# RGB-driver-v1.net
KiCad netlist of a schematic drawn in EAGLE
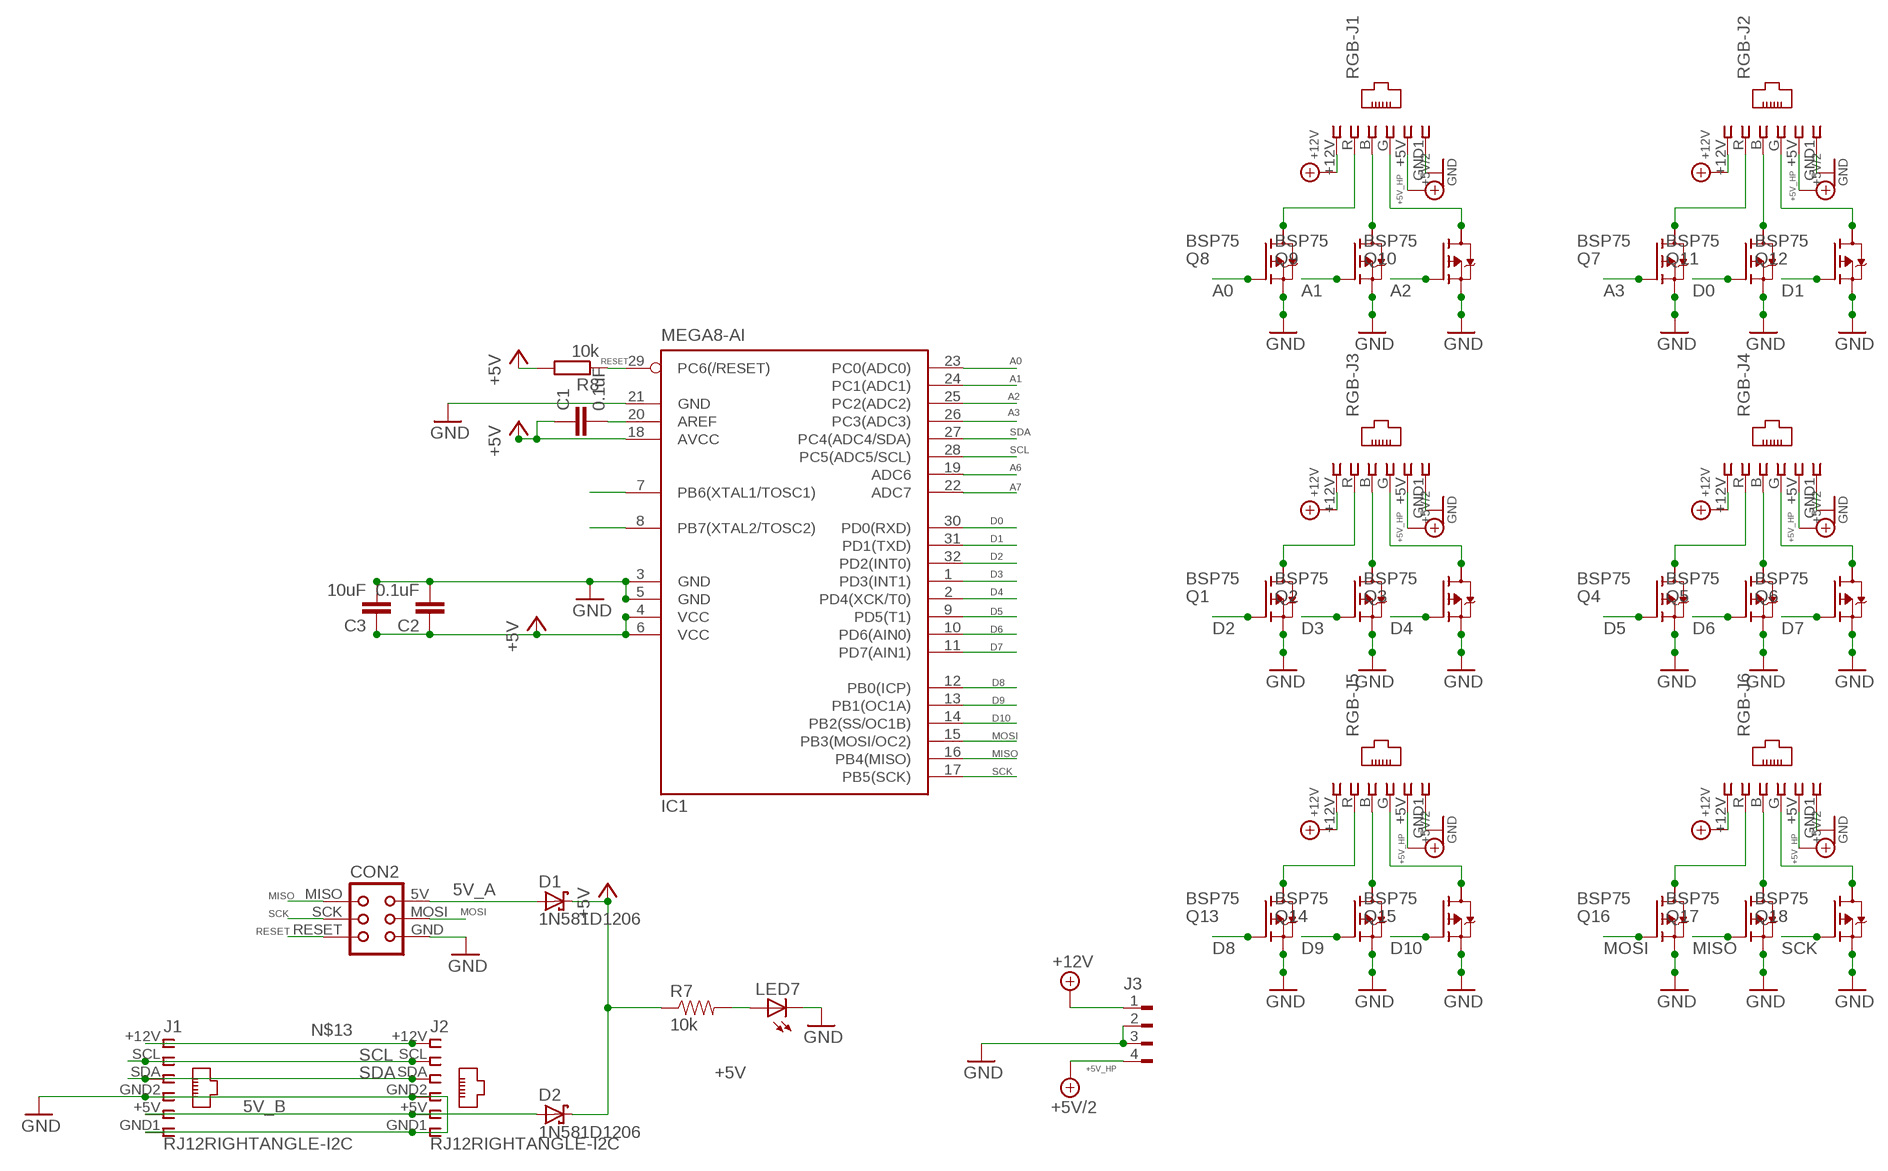
[diagram p0: schematic, sheet 1]

(export (version "E")
  (design (tool "Eeschema 10.0.6"))
  (components
    (comp (ref "C1")
      (value "0.1uF")
      (footprint "eagle-import:C1206")
      (libsource (lib "eagle-import") (part "C-EUC1206"))
    )
    (comp (ref "C2")
      (value "0.1uF")
      (footprint "eagle-import:C1206")
      (libsource (lib "eagle-import") (part "C-EUC1206"))
    )
    (comp (ref "C3")
      (value "10uF")
      (footprint "eagle-import:C1206")
      (libsource (lib "eagle-import") (part "C-EUC1206"))
    )
    (comp (ref "CON2")
      (value "TINYISPTAG")
      (footprint "eagle-import:TC2030-MCP")
      (libsource (lib "eagle-import") (part "TINYISPTAG"))
    )
    (comp (ref "D1")
      (value "1N581D1206")
      (footprint "eagle-import:LED-1206")
      (libsource (lib "eagle-import") (part "1N581D1206"))
    )
    (comp (ref "D2")
      (value "1N581D1206")
      (footprint "eagle-import:LED-1206")
      (libsource (lib "eagle-import") (part "1N581D1206"))
    )
    (comp (ref "IC1")
      (value "MEGA8-AI")
      (footprint "eagle-import:TQFP32-08")
      (fields (field (name "MPN") "ATMEGA8-16AU"))
      (libsource (lib "eagle-import") (part "MEGA8-AI"))
    )
    (comp (ref "J1")
      (value "RJ12RIGHTANGLE-I2C")
      (footprint "eagle-import:RJ12-RIGHTANGLE-I2C")
      (libsource (lib "eagle-import") (part "RJ12RIGHTANGLE-I2C"))
    )
    (comp (ref "J2")
      (value "RJ12RIGHTANGLE-I2C")
      (footprint "eagle-import:RJ12-RIGHTANGLE-I2C")
      (libsource (lib "eagle-import") (part "RJ12RIGHTANGLE-I2C"))
    )
    (comp (ref "J3")
      (value "FLOP-4W827001")
      (footprint "eagle-import:827001")
      (libsource (lib "eagle-import") (part "FLOP-4W827001"))
    )
    (comp (ref "LED7")
      (value "LEDCHIP-LED0603")
      (footprint "eagle-import:CHIP-LED0603")
      (libsource (lib "eagle-import") (part "LEDCHIP-LED0603"))
    )
    (comp (ref "Q1")
      (value "BSP75")
      (footprint "eagle-import:PG-SOT-223")
      (libsource (lib "eagle-import") (part "BSP613P"))
    )
    (comp (ref "Q2")
      (value "BSP75")
      (footprint "eagle-import:PG-SOT-223")
      (libsource (lib "eagle-import") (part "BSP613P"))
    )
    (comp (ref "Q3")
      (value "BSP75")
      (footprint "eagle-import:PG-SOT-223")
      (libsource (lib "eagle-import") (part "BSP613P"))
    )
    (comp (ref "Q4")
      (value "BSP75")
      (footprint "eagle-import:PG-SOT-223")
      (libsource (lib "eagle-import") (part "BSP613P"))
    )
    (comp (ref "Q5")
      (value "BSP75")
      (footprint "eagle-import:PG-SOT-223")
      (libsource (lib "eagle-import") (part "BSP613P"))
    )
    (comp (ref "Q6")
      (value "BSP75")
      (footprint "eagle-import:PG-SOT-223")
      (libsource (lib "eagle-import") (part "BSP613P"))
    )
    (comp (ref "Q7")
      (value "BSP75")
      (footprint "eagle-import:PG-SOT-223")
      (libsource (lib "eagle-import") (part "BSP613P"))
    )
    (comp (ref "Q8")
      (value "BSP75")
      (footprint "eagle-import:PG-SOT-223")
      (libsource (lib "eagle-import") (part "BSP613P"))
    )
    (comp (ref "Q9")
      (value "BSP75")
      (footprint "eagle-import:PG-SOT-223")
      (libsource (lib "eagle-import") (part "BSP613P"))
    )
    (comp (ref "Q10")
      (value "BSP75")
      (footprint "eagle-import:PG-SOT-223")
      (libsource (lib "eagle-import") (part "BSP613P"))
    )
    (comp (ref "Q11")
      (value "BSP75")
      (footprint "eagle-import:PG-SOT-223")
      (libsource (lib "eagle-import") (part "BSP613P"))
    )
    (comp (ref "Q12")
      (value "BSP75")
      (footprint "eagle-import:PG-SOT-223")
      (libsource (lib "eagle-import") (part "BSP613P"))
    )
    (comp (ref "Q13")
      (value "BSP75")
      (footprint "eagle-import:PG-SOT-223")
      (libsource (lib "eagle-import") (part "BSP613P"))
    )
    (comp (ref "Q14")
      (value "BSP75")
      (footprint "eagle-import:PG-SOT-223")
      (libsource (lib "eagle-import") (part "BSP613P"))
    )
    (comp (ref "Q15")
      (value "BSP75")
      (footprint "eagle-import:PG-SOT-223")
      (libsource (lib "eagle-import") (part "BSP613P"))
    )
    (comp (ref "Q16")
      (value "BSP75")
      (footprint "eagle-import:PG-SOT-223")
      (libsource (lib "eagle-import") (part "BSP613P"))
    )
    (comp (ref "Q17")
      (value "BSP75")
      (footprint "eagle-import:PG-SOT-223")
      (libsource (lib "eagle-import") (part "BSP613P"))
    )
    (comp (ref "Q18")
      (value "BSP75")
      (footprint "eagle-import:PG-SOT-223")
      (libsource (lib "eagle-import") (part "BSP613P"))
    )
    (comp (ref "R7")
      (value "10k")
      (footprint "eagle-import:0603-RES")
      (libsource (lib "eagle-import") (part "RESISTOR0603-RES"))
    )
    (comp (ref "R8")
      (value "10k")
      (footprint "eagle-import:M1206")
      (libsource (lib "eagle-import") (part "R-EU_M1206"))
    )
    (comp (ref "RGB-J1")
      (value "RJ12")
      (footprint "eagle-import:RJ12-STRAIGHT-RGB")
      (libsource (lib "eagle-import") (part "RJ12STRAIGHT-RGB"))
    )
    (comp (ref "RGB-J2")
      (value "RJ12")
      (footprint "eagle-import:RJ12-STRAIGHT-RGB")
      (libsource (lib "eagle-import") (part "RJ12STRAIGHT-RGB"))
    )
    (comp (ref "RGB-J3")
      (value "RJ12")
      (footprint "eagle-import:RJ12-STRAIGHT-RGB")
      (libsource (lib "eagle-import") (part "RJ12STRAIGHT-RGB"))
    )
    (comp (ref "RGB-J4")
      (value "RJ12")
      (footprint "eagle-import:RJ12-STRAIGHT-RGB")
      (libsource (lib "eagle-import") (part "RJ12STRAIGHT-RGB"))
    )
    (comp (ref "RGB-J5")
      (value "RJ12")
      (footprint "eagle-import:RJ12-STRAIGHT-RGB")
      (libsource (lib "eagle-import") (part "RJ12STRAIGHT-RGB"))
    )
    (comp (ref "RGB-J6")
      (value "RJ12")
      (footprint "eagle-import:RJ12-STRAIGHT-RGB")
      (libsource (lib "eagle-import") (part "RJ12STRAIGHT-RGB"))
    )
  )
  (nets
    (net (code "1") (name "+5V") (class "Default")
      (node (ref "C1") (pin "1") (pinfunction "1_1") (pintype "passive"))
      (node (ref "C2") (pin "1") (pinfunction "1_1") (pintype "passive"))
      (node (ref "C3") (pin "1") (pinfunction "1_1") (pintype "passive"))
      (node (ref "D1") (pin "C") (pinfunction "C_C") (pintype "passive"))
      (node (ref "D2") (pin "C") (pinfunction "C_C") (pintype "passive"))
      (node (ref "IC1") (pin "18") (pinfunction "AVCC_18") (pintype "power_in"))
      (node (ref "IC1") (pin "4") (pinfunction "VCC_4") (pintype "power_in"))
      (node (ref "IC1") (pin "6") (pinfunction "VCC_6") (pintype "power_in"))
      (node (ref "R7") (pin "1") (pinfunction "1_1") (pintype "passive"))
      (node (ref "R8") (pin "2") (pinfunction "2_2") (pintype "passive"))
    )
    (net (code "2") (name "+5V{slash}2") (class "Default")
      (node (ref "J3") (pin "4") (pinfunction "4_4") (pintype "passive"))
      (node (ref "RGB-J1") (pin "+5V") (pinfunction "5_+5V") (pintype "bidirectional"))
      (node (ref "RGB-J2") (pin "+5V") (pinfunction "5_+5V") (pintype "bidirectional"))
      (node (ref "RGB-J3") (pin "+5V") (pinfunction "5_+5V") (pintype "bidirectional"))
      (node (ref "RGB-J4") (pin "+5V") (pinfunction "5_+5V") (pintype "bidirectional"))
      (node (ref "RGB-J5") (pin "+5V") (pinfunction "5_+5V") (pintype "bidirectional"))
      (node (ref "RGB-J6") (pin "+5V") (pinfunction "5_+5V") (pintype "bidirectional"))
    )
    (net (code "3") (name "+12V") (class "Default")
      (node (ref "J3") (pin "1") (pinfunction "1_1") (pintype "passive"))
      (node (ref "RGB-J1") (pin "+12V") (pinfunction "1_+12V") (pintype "bidirectional"))
      (node (ref "RGB-J2") (pin "+12V") (pinfunction "1_+12V") (pintype "bidirectional"))
      (node (ref "RGB-J3") (pin "+12V") (pinfunction "1_+12V") (pintype "bidirectional"))
      (node (ref "RGB-J4") (pin "+12V") (pinfunction "1_+12V") (pintype "bidirectional"))
      (node (ref "RGB-J5") (pin "+12V") (pinfunction "1_+12V") (pintype "bidirectional"))
      (node (ref "RGB-J6") (pin "+12V") (pinfunction "1_+12V") (pintype "bidirectional"))
    )
    (net (code "4") (name "/5V_A") (class "Default")
      (node (ref "CON2") (pin "5V") (pinfunction "VCC_5V") (pintype "passive"))
      (node (ref "D1") (pin "A") (pinfunction "A_A") (pintype "passive"))
    )
    (net (code "5") (name "/5V_B") (class "Default")
      (node (ref "D2") (pin "A") (pinfunction "A_A") (pintype "passive"))
      (node (ref "J1") (pin "+5V") (pinfunction "5_+5V") (pintype "bidirectional"))
      (node (ref "J2") (pin "+5V") (pinfunction "5_+5V") (pintype "bidirectional"))
    )
    (net (code "6") (name "/A0") (class "Default")
      (node (ref "IC1") (pin "23") (pinfunction "PC0(ADC0)_23") (pintype "bidirectional"))
      (node (ref "Q8") (pin "1") (pinfunction "G_1") (pintype "passive"))
    )
    (net (code "7") (name "/A1") (class "Default")
      (node (ref "IC1") (pin "24") (pinfunction "PC1(ADC1)_24") (pintype "bidirectional"))
      (node (ref "Q9") (pin "1") (pinfunction "G_1") (pintype "passive"))
    )
    (net (code "8") (name "/A2") (class "Default")
      (node (ref "IC1") (pin "25") (pinfunction "PC2(ADC2)_25") (pintype "bidirectional"))
      (node (ref "Q10") (pin "1") (pinfunction "G_1") (pintype "passive"))
    )
    (net (code "9") (name "/A3") (class "Default")
      (node (ref "IC1") (pin "26") (pinfunction "PC3(ADC3)_26") (pintype "bidirectional"))
      (node (ref "Q7") (pin "1") (pinfunction "G_1") (pintype "passive"))
    )
    (net (code "10") (name "/A6") (class "Default")
      (node (ref "IC1") (pin "19") (pinfunction "ADC6_19") (pintype "bidirectional"))
    )
    (net (code "11") (name "/A7") (class "Default")
      (node (ref "IC1") (pin "22") (pinfunction "ADC7_22") (pintype "bidirectional"))
    )
    (net (code "12") (name "/D0") (class "Default")
      (node (ref "IC1") (pin "30") (pinfunction "PD0(RXD)_30") (pintype "bidirectional"))
      (node (ref "Q11") (pin "1") (pinfunction "G_1") (pintype "passive"))
    )
    (net (code "13") (name "/D1") (class "Default")
      (node (ref "IC1") (pin "31") (pinfunction "PD1(TXD)_31") (pintype "bidirectional"))
      (node (ref "Q12") (pin "1") (pinfunction "G_1") (pintype "passive"))
    )
    (net (code "14") (name "/D2") (class "Default")
      (node (ref "IC1") (pin "32") (pinfunction "PD2(INT0)_32") (pintype "bidirectional"))
      (node (ref "Q1") (pin "1") (pinfunction "G_1") (pintype "passive"))
    )
    (net (code "15") (name "/D3") (class "Default")
      (node (ref "IC1") (pin "1") (pinfunction "PD3(INT1)_1") (pintype "bidirectional"))
      (node (ref "Q2") (pin "1") (pinfunction "G_1") (pintype "passive"))
    )
    (net (code "16") (name "/D4") (class "Default")
      (node (ref "IC1") (pin "2") (pinfunction "PD4(XCK/T0)_2") (pintype "bidirectional"))
      (node (ref "Q3") (pin "1") (pinfunction "G_1") (pintype "passive"))
    )
    (net (code "17") (name "/D5") (class "Default")
      (node (ref "IC1") (pin "9") (pinfunction "PD5(T1)_9") (pintype "bidirectional"))
      (node (ref "Q4") (pin "1") (pinfunction "G_1") (pintype "passive"))
    )
    (net (code "18") (name "/D6") (class "Default")
      (node (ref "IC1") (pin "10") (pinfunction "PD6(AIN0)_10") (pintype "bidirectional"))
      (node (ref "Q5") (pin "1") (pinfunction "G_1") (pintype "passive"))
    )
    (net (code "19") (name "/D7") (class "Default")
      (node (ref "IC1") (pin "11") (pinfunction "PD7(AIN1)_11") (pintype "bidirectional"))
      (node (ref "Q6") (pin "1") (pinfunction "G_1") (pintype "passive"))
    )
    (net (code "20") (name "/D8") (class "Default")
      (node (ref "IC1") (pin "12") (pinfunction "PB0(ICP)_12") (pintype "bidirectional"))
      (node (ref "Q13") (pin "1") (pinfunction "G_1") (pintype "passive"))
    )
    (net (code "21") (name "/D9") (class "Default")
      (node (ref "IC1") (pin "13") (pinfunction "PB1(OC1A)_13") (pintype "bidirectional"))
      (node (ref "Q14") (pin "1") (pinfunction "G_1") (pintype "passive"))
    )
    (net (code "22") (name "/D10") (class "Default")
      (node (ref "IC1") (pin "14") (pinfunction "PB2(SS/OC1B)_14") (pintype "bidirectional"))
      (node (ref "Q15") (pin "1") (pinfunction "G_1") (pintype "passive"))
    )
    (net (code "23") (name "/MISO") (class "Default")
      (node (ref "CON2") (pin "MISO") (pinfunction "MISO_MISO") (pintype "passive"))
      (node (ref "IC1") (pin "16") (pinfunction "PB4(MISO)_16") (pintype "bidirectional"))
      (node (ref "Q17") (pin "1") (pinfunction "G_1") (pintype "passive"))
    )
    (net (code "24") (name "/MOSI") (class "Default")
      (node (ref "CON2") (pin "MOSI") (pinfunction "MOSI_MOSI") (pintype "passive"))
      (node (ref "IC1") (pin "15") (pinfunction "PB3(MOSI/OC2)_15") (pintype "bidirectional"))
      (node (ref "Q16") (pin "1") (pinfunction "G_1") (pintype "passive"))
    )
    (net (code "25") (name "/N$13") (class "Default")
      (node (ref "J1") (pin "+12V") (pinfunction "1_+12V") (pintype "bidirectional"))
      (node (ref "J2") (pin "+12V") (pinfunction "1_+12V") (pintype "bidirectional"))
    )
    (net (code "26") (name "/RESET") (class "Default")
      (node (ref "CON2") (pin "RESET") (pinfunction "RESET_RESET") (pintype "passive"))
      (node (ref "IC1") (pin "29") (pinfunction "PC6(/RESET)_29") (pintype "bidirectional"))
      (node (ref "R8") (pin "1") (pinfunction "1_1") (pintype "passive"))
    )
    (net (code "27") (name "/SCK") (class "Default")
      (node (ref "CON2") (pin "SCK") (pinfunction "SCK_SCK") (pintype "passive"))
      (node (ref "IC1") (pin "17") (pinfunction "PB5(SCK)_17") (pintype "bidirectional"))
      (node (ref "Q18") (pin "1") (pinfunction "G_1") (pintype "passive"))
    )
    (net (code "28") (name "/SCL") (class "Default")
      (node (ref "IC1") (pin "28") (pinfunction "PC5(ADC5/SCL)_28") (pintype "bidirectional"))
      (node (ref "J1") (pin "SCL") (pinfunction "2_SCL") (pintype "bidirectional"))
      (node (ref "J2") (pin "SCL") (pinfunction "2_SCL") (pintype "bidirectional"))
    )
    (net (code "29") (name "/SDA") (class "Default")
      (node (ref "IC1") (pin "27") (pinfunction "PC4(ADC4/SDA)_27") (pintype "bidirectional"))
      (node (ref "J1") (pin "SDA") (pinfunction "3_SDA") (pintype "bidirectional"))
      (node (ref "J2") (pin "SDA") (pinfunction "3_SDA") (pintype "bidirectional"))
    )
    (net (code "30") (name "GND") (class "Default")
      (node (ref "C2") (pin "2") (pinfunction "2_2") (pintype "passive"))
      (node (ref "C3") (pin "2") (pinfunction "2_2") (pintype "passive"))
      (node (ref "CON2") (pin "GND") (pinfunction "GND_GND") (pintype "passive"))
      (node (ref "IC1") (pin "21") (pinfunction "GND_21") (pintype "power_in"))
      (node (ref "IC1") (pin "3") (pinfunction "GND_3") (pintype "power_in"))
      (node (ref "IC1") (pin "5") (pinfunction "GND_5") (pintype "power_in"))
      (node (ref "J1") (pin "GND1") (pinfunction "6_GND1") (pintype "bidirectional"))
      (node (ref "J1") (pin "GND2") (pinfunction "4_GND2") (pintype "bidirectional"))
      (node (ref "J2") (pin "GND1") (pinfunction "6_GND1") (pintype "bidirectional"))
      (node (ref "J2") (pin "GND2") (pinfunction "4_GND2") (pintype "bidirectional"))
      (node (ref "J3") (pin "2") (pinfunction "2_2") (pintype "passive"))
      (node (ref "J3") (pin "3") (pinfunction "3_3") (pintype "passive"))
      (node (ref "LED7") (pin "C") (pinfunction "C_C") (pintype "passive"))
      (node (ref "Q1") (pin "3") (pinfunction "S_3") (pintype "passive"))
      (node (ref "Q10") (pin "3") (pinfunction "S_3") (pintype "passive"))
      (node (ref "Q11") (pin "3") (pinfunction "S_3") (pintype "passive"))
      (node (ref "Q12") (pin "3") (pinfunction "S_3") (pintype "passive"))
      (node (ref "Q13") (pin "3") (pinfunction "S_3") (pintype "passive"))
      (node (ref "Q14") (pin "3") (pinfunction "S_3") (pintype "passive"))
      (node (ref "Q15") (pin "3") (pinfunction "S_3") (pintype "passive"))
      (node (ref "Q16") (pin "3") (pinfunction "S_3") (pintype "passive"))
      (node (ref "Q17") (pin "3") (pinfunction "S_3") (pintype "passive"))
      (node (ref "Q18") (pin "3") (pinfunction "S_3") (pintype "passive"))
      (node (ref "Q2") (pin "3") (pinfunction "S_3") (pintype "passive"))
      (node (ref "Q3") (pin "3") (pinfunction "S_3") (pintype "passive"))
      (node (ref "Q4") (pin "3") (pinfunction "S_3") (pintype "passive"))
      (node (ref "Q5") (pin "3") (pinfunction "S_3") (pintype "passive"))
      (node (ref "Q6") (pin "3") (pinfunction "S_3") (pintype "passive"))
      (node (ref "Q7") (pin "3") (pinfunction "S_3") (pintype "passive"))
      (node (ref "Q8") (pin "3") (pinfunction "S_3") (pintype "passive"))
      (node (ref "Q9") (pin "3") (pinfunction "S_3") (pintype "passive"))
      (node (ref "RGB-J1") (pin "GND1") (pinfunction "6_GND1") (pintype "bidirectional"))
      (node (ref "RGB-J2") (pin "GND1") (pinfunction "6_GND1") (pintype "bidirectional"))
      (node (ref "RGB-J3") (pin "GND1") (pinfunction "6_GND1") (pintype "bidirectional"))
      (node (ref "RGB-J4") (pin "GND1") (pinfunction "6_GND1") (pintype "bidirectional"))
      (node (ref "RGB-J5") (pin "GND1") (pinfunction "6_GND1") (pintype "bidirectional"))
      (node (ref "RGB-J6") (pin "GND1") (pinfunction "6_GND1") (pintype "bidirectional"))
    )
    (net (code "31") (name "Net-(IC1-AREF)") (class "Default")
      (node (ref "C1") (pin "2") (pinfunction "2_2") (pintype "passive"))
      (node (ref "IC1") (pin "20") (pinfunction "AREF_20") (pintype "passive"))
    )
    (net (code "32") (name "Net-(LED7-PadA)") (class "Default")
      (node (ref "LED7") (pin "A") (pinfunction "A_A") (pintype "passive"))
      (node (ref "R7") (pin "2") (pinfunction "2_2") (pintype "passive"))
    )
    (net (code "33") (name "Net-(RGB-J1-2)") (class "Default")
      (node (ref "Q8") (pin "2") (pinfunction "D_2") (pintype "passive"))
      (node (ref "RGB-J1") (pin "R") (pinfunction "2_R") (pintype "bidirectional"))
    )
    (net (code "34") (name "Net-(RGB-J1-3)") (class "Default")
      (node (ref "Q9") (pin "2") (pinfunction "D_2") (pintype "passive"))
      (node (ref "RGB-J1") (pin "B") (pinfunction "3_B") (pintype "bidirectional"))
    )
    (net (code "35") (name "Net-(RGB-J1-4)") (class "Default")
      (node (ref "Q10") (pin "2") (pinfunction "D_2") (pintype "passive"))
      (node (ref "RGB-J1") (pin "G") (pinfunction "4_G") (pintype "bidirectional"))
    )
    (net (code "36") (name "Net-(RGB-J2-2)") (class "Default")
      (node (ref "Q7") (pin "2") (pinfunction "D_2") (pintype "passive"))
      (node (ref "RGB-J2") (pin "R") (pinfunction "2_R") (pintype "bidirectional"))
    )
    (net (code "37") (name "Net-(RGB-J2-3)") (class "Default")
      (node (ref "Q11") (pin "2") (pinfunction "D_2") (pintype "passive"))
      (node (ref "RGB-J2") (pin "B") (pinfunction "3_B") (pintype "bidirectional"))
    )
    (net (code "38") (name "Net-(RGB-J2-4)") (class "Default")
      (node (ref "Q12") (pin "2") (pinfunction "D_2") (pintype "passive"))
      (node (ref "RGB-J2") (pin "G") (pinfunction "4_G") (pintype "bidirectional"))
    )
    (net (code "39") (name "Net-(RGB-J3-2)") (class "Default")
      (node (ref "Q1") (pin "2") (pinfunction "D_2") (pintype "passive"))
      (node (ref "RGB-J3") (pin "R") (pinfunction "2_R") (pintype "bidirectional"))
    )
    (net (code "40") (name "Net-(RGB-J3-3)") (class "Default")
      (node (ref "Q2") (pin "2") (pinfunction "D_2") (pintype "passive"))
      (node (ref "RGB-J3") (pin "B") (pinfunction "3_B") (pintype "bidirectional"))
    )
    (net (code "41") (name "Net-(RGB-J3-4)") (class "Default")
      (node (ref "Q3") (pin "2") (pinfunction "D_2") (pintype "passive"))
      (node (ref "RGB-J3") (pin "G") (pinfunction "4_G") (pintype "bidirectional"))
    )
    (net (code "42") (name "Net-(RGB-J4-2)") (class "Default")
      (node (ref "Q4") (pin "2") (pinfunction "D_2") (pintype "passive"))
      (node (ref "RGB-J4") (pin "R") (pinfunction "2_R") (pintype "bidirectional"))
    )
    (net (code "43") (name "Net-(RGB-J4-3)") (class "Default")
      (node (ref "Q5") (pin "2") (pinfunction "D_2") (pintype "passive"))
      (node (ref "RGB-J4") (pin "B") (pinfunction "3_B") (pintype "bidirectional"))
    )
    (net (code "44") (name "Net-(RGB-J4-4)") (class "Default")
      (node (ref "Q6") (pin "2") (pinfunction "D_2") (pintype "passive"))
      (node (ref "RGB-J4") (pin "G") (pinfunction "4_G") (pintype "bidirectional"))
    )
    (net (code "45") (name "Net-(RGB-J5-2)") (class "Default")
      (node (ref "Q13") (pin "2") (pinfunction "D_2") (pintype "passive"))
      (node (ref "RGB-J5") (pin "R") (pinfunction "2_R") (pintype "bidirectional"))
    )
    (net (code "46") (name "Net-(RGB-J5-3)") (class "Default")
      (node (ref "Q14") (pin "2") (pinfunction "D_2") (pintype "passive"))
      (node (ref "RGB-J5") (pin "B") (pinfunction "3_B") (pintype "bidirectional"))
    )
    (net (code "47") (name "Net-(RGB-J5-4)") (class "Default")
      (node (ref "Q15") (pin "2") (pinfunction "D_2") (pintype "passive"))
      (node (ref "RGB-J5") (pin "G") (pinfunction "4_G") (pintype "bidirectional"))
    )
    (net (code "48") (name "Net-(RGB-J6-2)") (class "Default")
      (node (ref "Q16") (pin "2") (pinfunction "D_2") (pintype "passive"))
      (node (ref "RGB-J6") (pin "R") (pinfunction "2_R") (pintype "bidirectional"))
    )
    (net (code "49") (name "Net-(RGB-J6-3)") (class "Default")
      (node (ref "Q17") (pin "2") (pinfunction "D_2") (pintype "passive"))
      (node (ref "RGB-J6") (pin "B") (pinfunction "3_B") (pintype "bidirectional"))
    )
    (net (code "50") (name "Net-(RGB-J6-4)") (class "Default")
      (node (ref "Q18") (pin "2") (pinfunction "D_2") (pintype "passive"))
      (node (ref "RGB-J6") (pin "G") (pinfunction "4_G") (pintype "bidirectional"))
    )
    (net (code "51") (name "unconnected-(IC1-PB6(XTAL1{slash}TOSC1)-Pad7)") (class "Default")
      (node (ref "IC1") (pin "7") (pinfunction "PB6(XTAL1/TOSC1)_7") (pintype "bidirectional"))
    )
    (net (code "52") (name "unconnected-(IC1-PB7(XTAL2{slash}TOSC2)-Pad8)") (class "Default")
      (node (ref "IC1") (pin "8") (pinfunction "PB7(XTAL2/TOSC2)_8") (pintype "bidirectional"))
    )
    (net (code "53") (name "unconnected-(Q1-D-Pad4)") (class "Default")
      (node (ref "Q1") (pin "4") (pinfunction "D_4") (pintype "passive"))
    )
    (net (code "54") (name "unconnected-(Q2-D-Pad4)") (class "Default")
      (node (ref "Q2") (pin "4") (pinfunction "D_4") (pintype "passive"))
    )
    (net (code "55") (name "unconnected-(Q3-D-Pad4)") (class "Default")
      (node (ref "Q3") (pin "4") (pinfunction "D_4") (pintype "passive"))
    )
    (net (code "56") (name "unconnected-(Q4-D-Pad4)") (class "Default")
      (node (ref "Q4") (pin "4") (pinfunction "D_4") (pintype "passive"))
    )
    (net (code "57") (name "unconnected-(Q5-D-Pad4)") (class "Default")
      (node (ref "Q5") (pin "4") (pinfunction "D_4") (pintype "passive"))
    )
    (net (code "58") (name "unconnected-(Q6-D-Pad4)") (class "Default")
      (node (ref "Q6") (pin "4") (pinfunction "D_4") (pintype "passive"))
    )
    (net (code "59") (name "unconnected-(Q7-D-Pad4)") (class "Default")
      (node (ref "Q7") (pin "4") (pinfunction "D_4") (pintype "passive"))
    )
    (net (code "60") (name "unconnected-(Q8-D-Pad4)") (class "Default")
      (node (ref "Q8") (pin "4") (pinfunction "D_4") (pintype "passive"))
    )
    (net (code "61") (name "unconnected-(Q9-D-Pad4)") (class "Default")
      (node (ref "Q9") (pin "4") (pinfunction "D_4") (pintype "passive"))
    )
    (net (code "62") (name "unconnected-(Q10-D-Pad4)") (class "Default")
      (node (ref "Q10") (pin "4") (pinfunction "D_4") (pintype "passive"))
    )
    (net (code "63") (name "unconnected-(Q11-D-Pad4)") (class "Default")
      (node (ref "Q11") (pin "4") (pinfunction "D_4") (pintype "passive"))
    )
    (net (code "64") (name "unconnected-(Q12-D-Pad4)") (class "Default")
      (node (ref "Q12") (pin "4") (pinfunction "D_4") (pintype "passive"))
    )
    (net (code "65") (name "unconnected-(Q13-D-Pad4)") (class "Default")
      (node (ref "Q13") (pin "4") (pinfunction "D_4") (pintype "passive"))
    )
    (net (code "66") (name "unconnected-(Q14-D-Pad4)") (class "Default")
      (node (ref "Q14") (pin "4") (pinfunction "D_4") (pintype "passive"))
    )
    (net (code "67") (name "unconnected-(Q15-D-Pad4)") (class "Default")
      (node (ref "Q15") (pin "4") (pinfunction "D_4") (pintype "passive"))
    )
    (net (code "68") (name "unconnected-(Q16-D-Pad4)") (class "Default")
      (node (ref "Q16") (pin "4") (pinfunction "D_4") (pintype "passive"))
    )
    (net (code "69") (name "unconnected-(Q17-D-Pad4)") (class "Default")
      (node (ref "Q17") (pin "4") (pinfunction "D_4") (pintype "passive"))
    )
    (net (code "70") (name "unconnected-(Q18-D-Pad4)") (class "Default")
      (node (ref "Q18") (pin "4") (pinfunction "D_4") (pintype "passive"))
    )
  )
)
